# Half_Inch_VCO__Eval.net
KiCad netlist of a schematic drawn in EAGLE
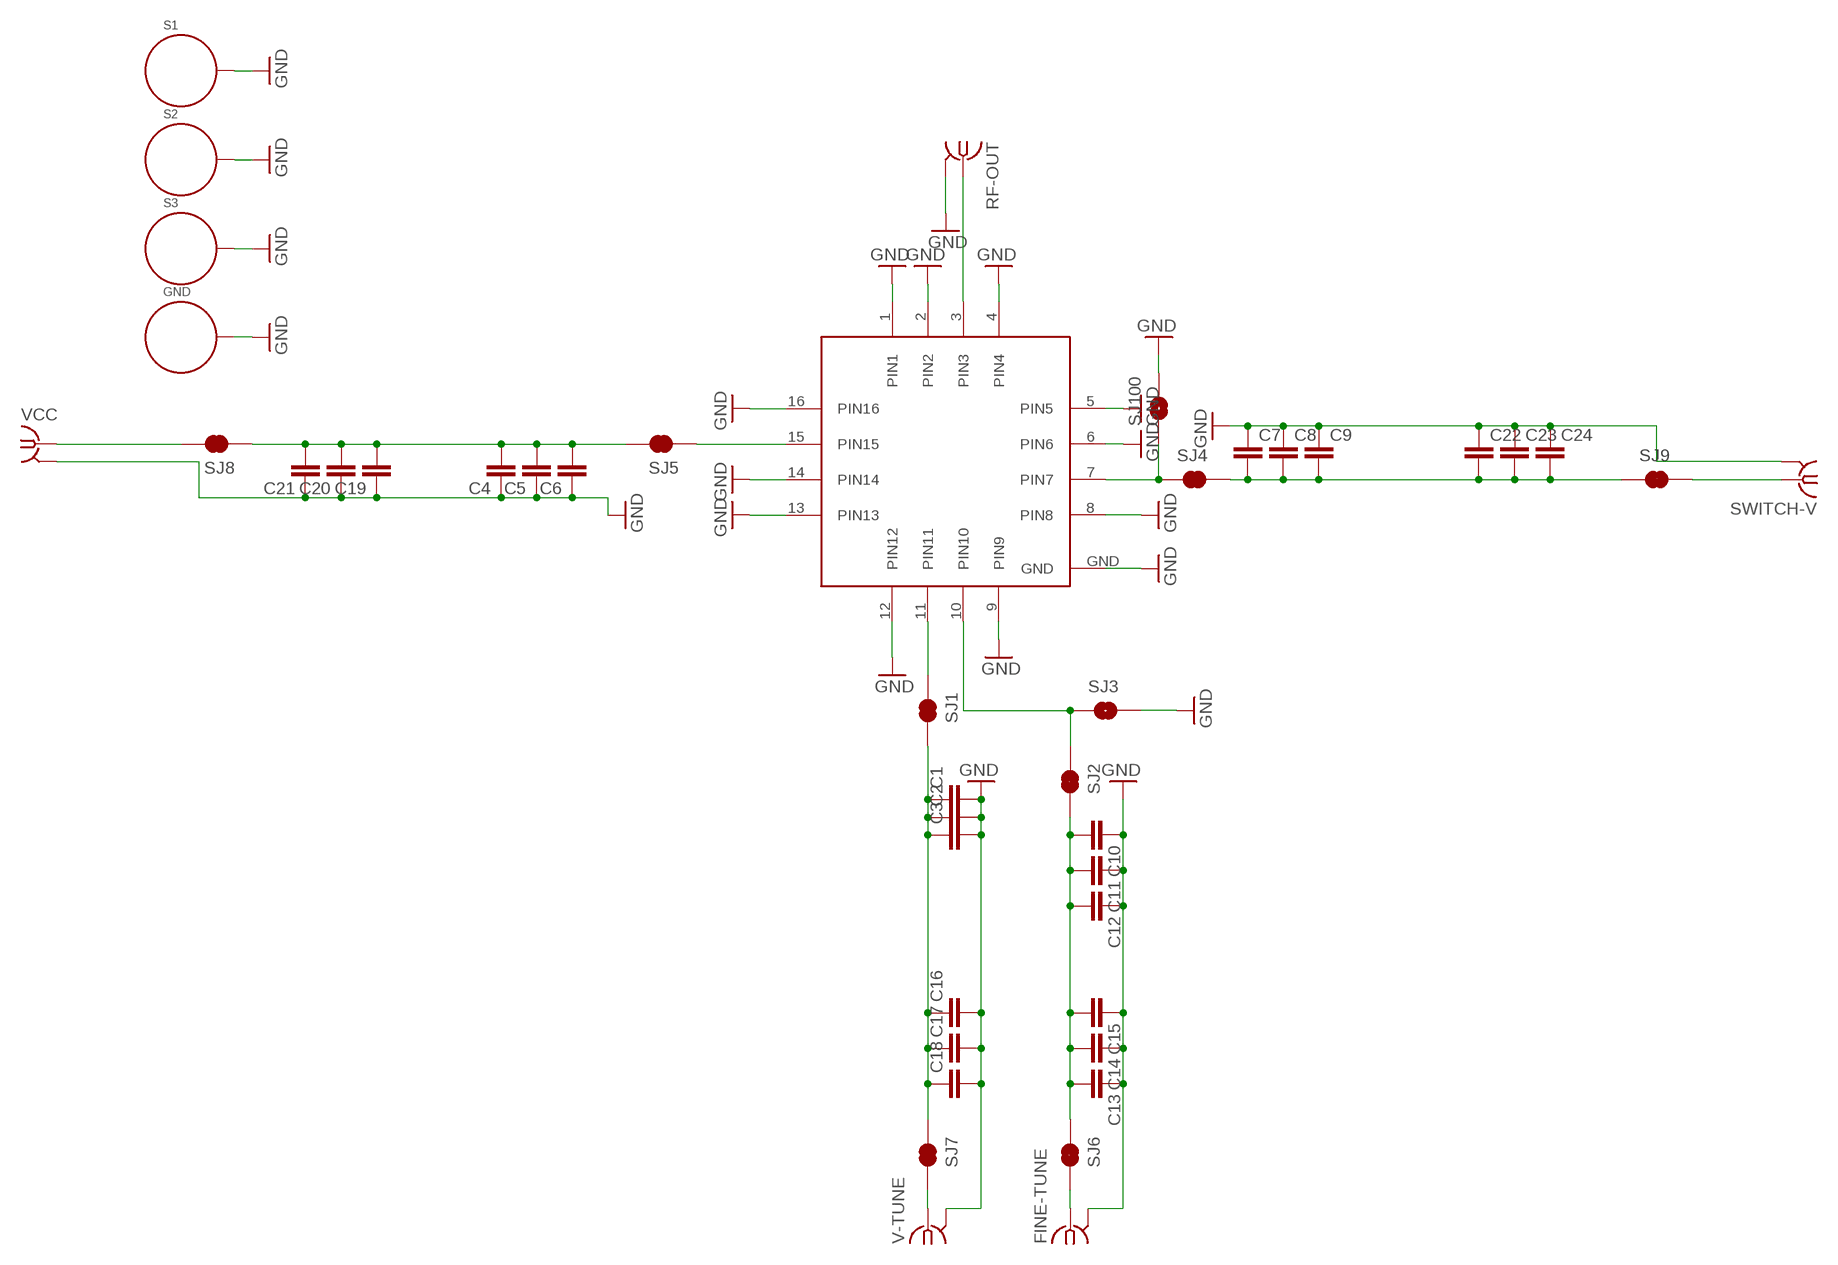
[diagram p0: schematic, sheet 1]

(export (version "E")
  (design (tool "Eeschema 10.0.6"))
  (components
    (comp (ref "C1")
      (value "CAP0402-CAP")
      (footprint "eagle-import:0402-CAP")
      (libsource (lib "eagle-import") (part "CAP0402-CAP"))
    )
    (comp (ref "C2")
      (value "CAP0402-CAP")
      (footprint "eagle-import:0402-CAP")
      (libsource (lib "eagle-import") (part "CAP0402-CAP"))
    )
    (comp (ref "C3")
      (value "CAP0402-CAP")
      (footprint "eagle-import:0402-CAP")
      (libsource (lib "eagle-import") (part "CAP0402-CAP"))
    )
    (comp (ref "C4")
      (value "CAP0402-CAP")
      (footprint "eagle-import:0402-CAP")
      (libsource (lib "eagle-import") (part "CAP0402-CAP"))
    )
    (comp (ref "C5")
      (value "CAP0402-CAP")
      (footprint "eagle-import:0402-CAP")
      (libsource (lib "eagle-import") (part "CAP0402-CAP"))
    )
    (comp (ref "C6")
      (value "CAP0402-CAP")
      (footprint "eagle-import:0402-CAP")
      (libsource (lib "eagle-import") (part "CAP0402-CAP"))
    )
    (comp (ref "C7")
      (value "CAP0402-CAP")
      (footprint "eagle-import:0402-CAP")
      (libsource (lib "eagle-import") (part "CAP0402-CAP"))
    )
    (comp (ref "C8")
      (value "CAP0402-CAP")
      (footprint "eagle-import:0402-CAP")
      (libsource (lib "eagle-import") (part "CAP0402-CAP"))
    )
    (comp (ref "C9")
      (value "CAP0402-CAP")
      (footprint "eagle-import:0402-CAP")
      (libsource (lib "eagle-import") (part "CAP0402-CAP"))
    )
    (comp (ref "C10")
      (value "CAP0402-CAP")
      (footprint "eagle-import:0402-CAP")
      (libsource (lib "eagle-import") (part "CAP0402-CAP"))
    )
    (comp (ref "C11")
      (value "CAP0402-CAP")
      (footprint "eagle-import:0402-CAP")
      (libsource (lib "eagle-import") (part "CAP0402-CAP"))
    )
    (comp (ref "C12")
      (value "CAP0402-CAP")
      (footprint "eagle-import:0402-CAP")
      (libsource (lib "eagle-import") (part "CAP0402-CAP"))
    )
    (comp (ref "C13")
      (value "CAP0402-CAP")
      (footprint "eagle-import:0402-CAP")
      (libsource (lib "eagle-import") (part "CAP0402-CAP"))
    )
    (comp (ref "C14")
      (value "CAP0402-CAP")
      (footprint "eagle-import:0402-CAP")
      (libsource (lib "eagle-import") (part "CAP0402-CAP"))
    )
    (comp (ref "C15")
      (value "CAP0402-CAP")
      (footprint "eagle-import:0402-CAP")
      (libsource (lib "eagle-import") (part "CAP0402-CAP"))
    )
    (comp (ref "C16")
      (value "CAP0402-CAP")
      (footprint "eagle-import:0402-CAP")
      (libsource (lib "eagle-import") (part "CAP0402-CAP"))
    )
    (comp (ref "C17")
      (value "CAP0402-CAP")
      (footprint "eagle-import:0402-CAP")
      (libsource (lib "eagle-import") (part "CAP0402-CAP"))
    )
    (comp (ref "C18")
      (value "CAP0402-CAP")
      (footprint "eagle-import:0402-CAP")
      (libsource (lib "eagle-import") (part "CAP0402-CAP"))
    )
    (comp (ref "C19")
      (value "CAP0402-CAP")
      (footprint "eagle-import:0402-CAP")
      (libsource (lib "eagle-import") (part "CAP0402-CAP"))
    )
    (comp (ref "C20")
      (value "CAP0402-CAP")
      (footprint "eagle-import:0402-CAP")
      (libsource (lib "eagle-import") (part "CAP0402-CAP"))
    )
    (comp (ref "C21")
      (value "CAP0402-CAP")
      (footprint "eagle-import:0402-CAP")
      (libsource (lib "eagle-import") (part "CAP0402-CAP"))
    )
    (comp (ref "C22")
      (value "CAP0402-CAP")
      (footprint "eagle-import:0402-CAP")
      (libsource (lib "eagle-import") (part "CAP0402-CAP"))
    )
    (comp (ref "C23")
      (value "CAP0402-CAP")
      (footprint "eagle-import:0402-CAP")
      (libsource (lib "eagle-import") (part "CAP0402-CAP"))
    )
    (comp (ref "C24")
      (value "CAP0402-CAP")
      (footprint "eagle-import:0402-CAP")
      (libsource (lib "eagle-import") (part "CAP0402-CAP"))
    )
    (comp (ref "FINE-TUNE")
      (value "SMA-142-0701-801/806")
      (footprint "eagle-import:J502-ND-142-0701-801_806")
      (fields (field (name "MF") "JOHNSON COMPONENTS") (field (name "MPN") "142-0701-801"))
      (libsource (lib "eagle-import") (part "con-coax_SMA-142-0701-801/806"))
    )
    (comp (ref "GND")
      (value "STANDOFF_ELECTRICAL")
      (footprint "eagle-import:STANDOFF-ELECTRICAL")
      (libsource (lib "eagle-import") (part "STANDOFF_ELECTRICAL"))
    )
    (comp (ref "RF-OUT")
      (value "SMA-142-0701-871/876")
      (footprint "eagle-import:J502-ND-142-0701-871_876")
      (fields (field (name "MF") "JOHNSON COMPONENTS") (field (name "MPN") "142-0701-871"))
      (libsource (lib "eagle-import") (part "SMA-142-0701-871/876"))
    )
    (comp (ref "S1")
      (value "STANDOFF_ELECTRICAL")
      (footprint "eagle-import:STANDOFF-ELECTRICAL")
      (libsource (lib "eagle-import") (part "STANDOFF_ELECTRICAL"))
    )
    (comp (ref "S2")
      (value "STANDOFF_ELECTRICAL")
      (footprint "eagle-import:STANDOFF-ELECTRICAL")
      (libsource (lib "eagle-import") (part "STANDOFF_ELECTRICAL"))
    )
    (comp (ref "S3")
      (value "STANDOFF_ELECTRICAL")
      (footprint "eagle-import:STANDOFF-ELECTRICAL")
      (libsource (lib "eagle-import") (part "STANDOFF_ELECTRICAL"))
    )
    (comp (ref "SJ1")
      (value "JUMPER-PAD-2-NC_BY_TRACE")
      (footprint "eagle-import:PAD-JUMPER-2-NC_BY_TRACE_YES_SILK")
      (libsource (lib "eagle-import") (part "JUMPER-PAD-2-NC_BY_TRACE"))
    )
    (comp (ref "SJ2")
      (value "JUMPER-PAD-2-NC_BY_TRACE")
      (footprint "eagle-import:PAD-JUMPER-2-NC_BY_TRACE_YES_SILK")
      (libsource (lib "eagle-import") (part "JUMPER-PAD-2-NC_BY_TRACE"))
    )
    (comp (ref "SJ3")
      (value "SOLDERJUMPER-OLDNC2")
      (footprint "eagle-import:SJ_2S-NOTRACE")
      (libsource (lib "eagle-import") (part "SOLDERJUMPER-OLDNC2"))
    )
    (comp (ref "SJ4")
      (value "JUMPER-PAD-2-NC_BY_TRACE")
      (footprint "eagle-import:PAD-JUMPER-2-NC_BY_TRACE_YES_SILK")
      (libsource (lib "eagle-import") (part "JUMPER-PAD-2-NC_BY_TRACE"))
    )
    (comp (ref "SJ5")
      (value "JUMPER-PAD-2-NC_BY_TRACE")
      (footprint "eagle-import:PAD-JUMPER-2-NC_BY_TRACE_YES_SILK")
      (libsource (lib "eagle-import") (part "JUMPER-PAD-2-NC_BY_TRACE"))
    )
    (comp (ref "SJ6")
      (value "JUMPER-PAD-2-NC_BY_TRACE")
      (footprint "eagle-import:PAD-JUMPER-2-NC_BY_TRACE_YES_SILK")
      (libsource (lib "eagle-import") (part "JUMPER-PAD-2-NC_BY_TRACE"))
    )
    (comp (ref "SJ7")
      (value "JUMPER-PAD-2-NC_BY_TRACE")
      (footprint "eagle-import:PAD-JUMPER-2-NC_BY_TRACE_YES_SILK")
      (libsource (lib "eagle-import") (part "JUMPER-PAD-2-NC_BY_TRACE"))
    )
    (comp (ref "SJ8")
      (value "JUMPER-PAD-2-NC_BY_TRACE")
      (footprint "eagle-import:PAD-JUMPER-2-NC_BY_TRACE_YES_SILK")
      (libsource (lib "eagle-import") (part "JUMPER-PAD-2-NC_BY_TRACE"))
    )
    (comp (ref "SJ9")
      (value "JUMPER-PAD-2-NC_BY_TRACE")
      (footprint "eagle-import:PAD-JUMPER-2-NC_BY_TRACE_YES_SILK")
      (libsource (lib "eagle-import") (part "JUMPER-PAD-2-NC_BY_TRACE"))
    )
    (comp (ref "SJ100")
      (value "SOLDERJUMPER-OLDNC2")
      (footprint "eagle-import:SJ_2S-NOTRACE")
      (libsource (lib "eagle-import") (part "SOLDERJUMPER-OLDNC2"))
    )
    (comp (ref "SWITCH-V")
      (value "SMA-142-0701-801/806")
      (footprint "eagle-import:J502-ND-142-0701-801_806")
      (fields (field (name "MF") "JOHNSON COMPONENTS") (field (name "MPN") "142-0701-801"))
      (libsource (lib "eagle-import") (part "con-coax_SMA-142-0701-801/806"))
    )
    (comp (ref "U$1")
      (value "RFVC6406")
      (footprint "eagle-import:RFVC6406")
      (libsource (lib "eagle-import") (part "RFVC6406"))
    )
    (comp (ref "V-TUNE")
      (value "SMA-142-0701-801/806")
      (footprint "eagle-import:J502-ND-142-0701-801_806")
      (fields (field (name "MF") "JOHNSON COMPONENTS") (field (name "MPN") "142-0701-801"))
      (libsource (lib "eagle-import") (part "con-coax_SMA-142-0701-801/806"))
    )
    (comp (ref "VCC")
      (value "SMA-142-0701-801/806")
      (footprint "eagle-import:J502-ND-142-0701-801_806")
      (fields (field (name "MF") "JOHNSON COMPONENTS") (field (name "MPN") "142-0701-801"))
      (libsource (lib "eagle-import") (part "con-coax_SMA-142-0701-801/806"))
    )
  )
  (nets
    (net (code "1") (name "GND") (class "Default")
      (node (ref "C1") (pin "2") (pinfunction "2_2") (pintype "passive"))
      (node (ref "C10") (pin "1") (pinfunction "1_1") (pintype "passive"))
      (node (ref "C11") (pin "1") (pinfunction "1_1") (pintype "passive"))
      (node (ref "C12") (pin "1") (pinfunction "1_1") (pintype "passive"))
      (node (ref "C13") (pin "1") (pinfunction "1_1") (pintype "passive"))
      (node (ref "C14") (pin "1") (pinfunction "1_1") (pintype "passive"))
      (node (ref "C15") (pin "1") (pinfunction "1_1") (pintype "passive"))
      (node (ref "C16") (pin "2") (pinfunction "2_2") (pintype "passive"))
      (node (ref "C17") (pin "2") (pinfunction "2_2") (pintype "passive"))
      (node (ref "C18") (pin "2") (pinfunction "2_2") (pintype "passive"))
      (node (ref "C19") (pin "1") (pinfunction "1_1") (pintype "passive"))
      (node (ref "C2") (pin "2") (pinfunction "2_2") (pintype "passive"))
      (node (ref "C20") (pin "1") (pinfunction "1_1") (pintype "passive"))
      (node (ref "C21") (pin "1") (pinfunction "1_1") (pintype "passive"))
      (node (ref "C22") (pin "1") (pinfunction "1_1") (pintype "passive"))
      (node (ref "C23") (pin "1") (pinfunction "1_1") (pintype "passive"))
      (node (ref "C24") (pin "1") (pinfunction "1_1") (pintype "passive"))
      (node (ref "C3") (pin "2") (pinfunction "2_2") (pintype "passive"))
      (node (ref "C4") (pin "1") (pinfunction "1_1") (pintype "passive"))
      (node (ref "C5") (pin "1") (pinfunction "1_1") (pintype "passive"))
      (node (ref "C6") (pin "1") (pinfunction "1_1") (pintype "passive"))
      (node (ref "C7") (pin "1") (pinfunction "1_1") (pintype "passive"))
      (node (ref "C8") (pin "1") (pinfunction "1_1") (pintype "passive"))
      (node (ref "C9") (pin "1") (pinfunction "1_1") (pintype "passive"))
      (node (ref "FINE-TUNE") (pin "G@1") (pinfunction "2_G@1") (pintype "passive"))
      (node (ref "FINE-TUNE") (pin "G@2") (pinfunction "2_G@2") (pintype "passive"))
      (node (ref "FINE-TUNE") (pin "G@3") (pinfunction "2_G@3") (pintype "passive"))
      (node (ref "FINE-TUNE") (pin "G@4") (pinfunction "2_G@4") (pintype "passive"))
      (node (ref "GND") (pin "P1") (pinfunction "P$1_P1") (pintype "bidirectional"))
      (node (ref "RF-OUT") (pin "G@1") (pinfunction "2_G@1") (pintype "passive"))
      (node (ref "RF-OUT") (pin "G@2") (pinfunction "2_G@2") (pintype "passive"))
      (node (ref "RF-OUT") (pin "G@3") (pinfunction "2_G@3") (pintype "passive"))
      (node (ref "RF-OUT") (pin "G@4") (pinfunction "2_G@4") (pintype "passive"))
      (node (ref "S1") (pin "P1") (pinfunction "P$1_P1") (pintype "bidirectional"))
      (node (ref "S2") (pin "P1") (pinfunction "P$1_P1") (pintype "bidirectional"))
      (node (ref "S3") (pin "P1") (pinfunction "P$1_P1") (pintype "bidirectional"))
      (node (ref "SJ100") (pin "2") (pinfunction "2_2") (pintype "passive"))
      (node (ref "SJ3") (pin "2") (pinfunction "2_2") (pintype "passive"))
      (node (ref "SWITCH-V") (pin "G@1") (pinfunction "2_G@1") (pintype "passive"))
      (node (ref "SWITCH-V") (pin "G@2") (pinfunction "2_G@2") (pintype "passive"))
      (node (ref "SWITCH-V") (pin "G@3") (pinfunction "2_G@3") (pintype "passive"))
      (node (ref "SWITCH-V") (pin "G@4") (pinfunction "2_G@4") (pintype "passive"))
      (node (ref "U$1") (pin "1") (pinfunction "PIN1_1") (pintype "bidirectional"))
      (node (ref "U$1") (pin "12") (pinfunction "PIN12_12") (pintype "bidirectional"))
      (node (ref "U$1") (pin "13") (pinfunction "PIN13_13") (pintype "bidirectional"))
      (node (ref "U$1") (pin "14") (pinfunction "PIN14_14") (pintype "bidirectional"))
      (node (ref "U$1") (pin "16") (pinfunction "PIN16_16") (pintype "bidirectional"))
      (node (ref "U$1") (pin "2") (pinfunction "PIN2_2") (pintype "bidirectional"))
      (node (ref "U$1") (pin "4") (pinfunction "PIN4_4") (pintype "bidirectional"))
      (node (ref "U$1") (pin "5") (pinfunction "PIN5_5") (pintype "bidirectional"))
      (node (ref "U$1") (pin "6") (pinfunction "PIN6_6") (pintype "bidirectional"))
      (node (ref "U$1") (pin "8") (pinfunction "PIN8_8") (pintype "bidirectional"))
      (node (ref "U$1") (pin "9") (pinfunction "PIN9_9") (pintype "bidirectional"))
      (node (ref "U$1") (pin "GND") (pinfunction "GND_GND") (pintype "bidirectional"))
      (node (ref "V-TUNE") (pin "G@1") (pinfunction "2_G@1") (pintype "passive"))
      (node (ref "V-TUNE") (pin "G@2") (pinfunction "2_G@2") (pintype "passive"))
      (node (ref "V-TUNE") (pin "G@3") (pinfunction "2_G@3") (pintype "passive"))
      (node (ref "V-TUNE") (pin "G@4") (pinfunction "2_G@4") (pintype "passive"))
      (node (ref "VCC") (pin "G@1") (pinfunction "2_G@1") (pintype "passive"))
      (node (ref "VCC") (pin "G@2") (pinfunction "2_G@2") (pintype "passive"))
      (node (ref "VCC") (pin "G@3") (pinfunction "2_G@3") (pintype "passive"))
      (node (ref "VCC") (pin "G@4") (pinfunction "2_G@4") (pintype "passive"))
    )
    (net (code "2") (name "Net-(C1-Pad1)") (class "Default")
      (node (ref "C1") (pin "1") (pinfunction "1_1") (pintype "passive"))
      (node (ref "C16") (pin "1") (pinfunction "1_1") (pintype "passive"))
      (node (ref "C17") (pin "1") (pinfunction "1_1") (pintype "passive"))
      (node (ref "C18") (pin "1") (pinfunction "1_1") (pintype "passive"))
      (node (ref "C2") (pin "1") (pinfunction "1_1") (pintype "passive"))
      (node (ref "C3") (pin "1") (pinfunction "1_1") (pintype "passive"))
      (node (ref "SJ1") (pin "2") (pinfunction "2_2") (pintype "passive"))
      (node (ref "SJ7") (pin "1") (pinfunction "1_1") (pintype "passive"))
    )
    (net (code "3") (name "Net-(C10-Pad2)") (class "Default")
      (node (ref "C10") (pin "2") (pinfunction "2_2") (pintype "passive"))
      (node (ref "C11") (pin "2") (pinfunction "2_2") (pintype "passive"))
      (node (ref "C12") (pin "2") (pinfunction "2_2") (pintype "passive"))
      (node (ref "C13") (pin "2") (pinfunction "2_2") (pintype "passive"))
      (node (ref "C14") (pin "2") (pinfunction "2_2") (pintype "passive"))
      (node (ref "C15") (pin "2") (pinfunction "2_2") (pintype "passive"))
      (node (ref "SJ2") (pin "2") (pinfunction "2_2") (pintype "passive"))
      (node (ref "SJ6") (pin "1") (pinfunction "1_1") (pintype "passive"))
    )
    (net (code "4") (name "Net-(C19-Pad2)") (class "Default")
      (node (ref "C19") (pin "2") (pinfunction "2_2") (pintype "passive"))
      (node (ref "C20") (pin "2") (pinfunction "2_2") (pintype "passive"))
      (node (ref "C21") (pin "2") (pinfunction "2_2") (pintype "passive"))
      (node (ref "C4") (pin "2") (pinfunction "2_2") (pintype "passive"))
      (node (ref "C5") (pin "2") (pinfunction "2_2") (pintype "passive"))
      (node (ref "C6") (pin "2") (pinfunction "2_2") (pintype "passive"))
      (node (ref "SJ5") (pin "2") (pinfunction "2_2") (pintype "passive"))
      (node (ref "SJ8") (pin "1") (pinfunction "1_1") (pintype "passive"))
    )
    (net (code "5") (name "Net-(C22-Pad2)") (class "Default")
      (node (ref "C22") (pin "2") (pinfunction "2_2") (pintype "passive"))
      (node (ref "C23") (pin "2") (pinfunction "2_2") (pintype "passive"))
      (node (ref "C24") (pin "2") (pinfunction "2_2") (pintype "passive"))
      (node (ref "C7") (pin "2") (pinfunction "2_2") (pintype "passive"))
      (node (ref "C8") (pin "2") (pinfunction "2_2") (pintype "passive"))
      (node (ref "C9") (pin "2") (pinfunction "2_2") (pintype "passive"))
      (node (ref "SJ4") (pin "2") (pinfunction "2_2") (pintype "passive"))
      (node (ref "SJ9") (pin "1") (pinfunction "1_1") (pintype "passive"))
    )
    (net (code "6") (name "Net-(FINE-TUNE-Pad1)") (class "Default")
      (node (ref "FINE-TUNE") (pin "1") (pinfunction "1_1") (pintype "passive"))
      (node (ref "SJ6") (pin "2") (pinfunction "2_2") (pintype "passive"))
    )
    (net (code "7") (name "Net-(SJ7-Pad2)") (class "Default")
      (node (ref "SJ7") (pin "2") (pinfunction "2_2") (pintype "passive"))
      (node (ref "V-TUNE") (pin "1") (pinfunction "1_1") (pintype "passive"))
    )
    (net (code "8") (name "Net-(SJ8-Pad2)") (class "Default")
      (node (ref "SJ8") (pin "2") (pinfunction "2_2") (pintype "passive"))
      (node (ref "VCC") (pin "1") (pinfunction "1_1") (pintype "passive"))
    )
    (net (code "9") (name "Net-(SJ9-Pad2)") (class "Default")
      (node (ref "SJ9") (pin "2") (pinfunction "2_2") (pintype "passive"))
      (node (ref "SWITCH-V") (pin "1") (pinfunction "1_1") (pintype "passive"))
    )
    (net (code "10") (name "Net-(U$1-PIN3)") (class "Default")
      (node (ref "RF-OUT") (pin "1") (pinfunction "1_1") (pintype "passive"))
      (node (ref "U$1") (pin "3") (pinfunction "PIN3_3") (pintype "bidirectional"))
    )
    (net (code "11") (name "Net-(U$1-PIN7)") (class "Default")
      (node (ref "SJ100") (pin "1") (pinfunction "1_1") (pintype "passive"))
      (node (ref "SJ4") (pin "1") (pinfunction "1_1") (pintype "passive"))
      (node (ref "U$1") (pin "7") (pinfunction "PIN7_7") (pintype "bidirectional"))
    )
    (net (code "12") (name "Net-(U$1-PIN10)") (class "Default")
      (node (ref "SJ2") (pin "1") (pinfunction "1_1") (pintype "passive"))
      (node (ref "SJ3") (pin "1") (pinfunction "1_1") (pintype "passive"))
      (node (ref "U$1") (pin "10") (pinfunction "PIN10_10") (pintype "bidirectional"))
    )
    (net (code "13") (name "Net-(U$1-PIN11)") (class "Default")
      (node (ref "SJ1") (pin "1") (pinfunction "1_1") (pintype "passive"))
      (node (ref "U$1") (pin "11") (pinfunction "PIN11_11") (pintype "bidirectional"))
    )
    (net (code "14") (name "Net-(U$1-PIN15)") (class "Default")
      (node (ref "SJ5") (pin "1") (pinfunction "1_1") (pintype "passive"))
      (node (ref "U$1") (pin "15") (pinfunction "PIN15_15") (pintype "bidirectional"))
    )
  )
)
